# encoder_board.net
KiCad netlist of a schematic drawn in EAGLE
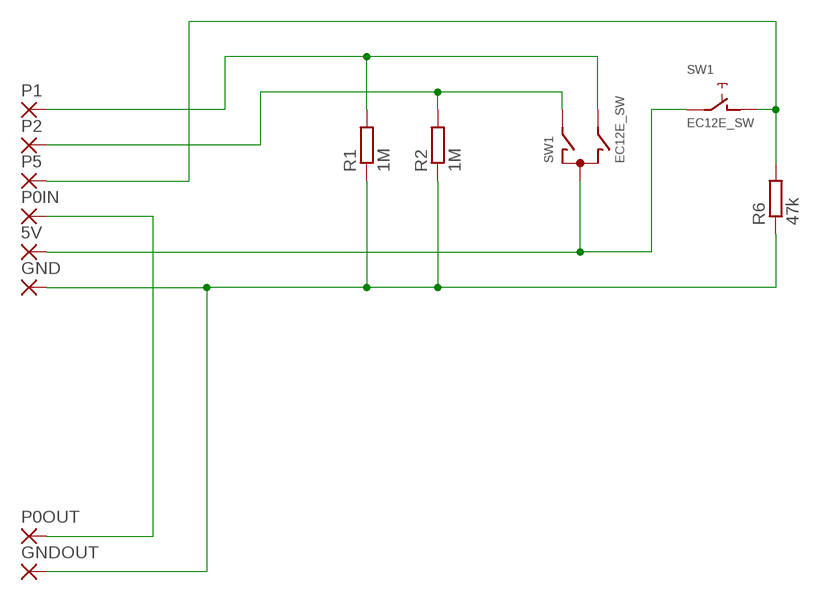
[diagram p0: schematic, sheet 1]

(export (version "E")
  (design (tool "Eeschema 10.0.6"))
  (components
    (comp (ref "5V")
      (value "2,54/0,8")
      (footprint "eagle-import:2,54_0,8")
      (libsource (lib "eagle-import") (part "2,54/0,8"))
    )
    (comp (ref "GND")
      (value "2,54/0,8")
      (footprint "eagle-import:2,54_0,8")
      (libsource (lib "eagle-import") (part "2,54/0,8"))
    )
    (comp (ref "GNDOUT")
      (value "2,54/0,8")
      (footprint "eagle-import:2,54_0,8")
      (libsource (lib "eagle-import") (part "2,54/0,8"))
    )
    (comp (ref "P0IN")
      (value "2,54/0,8")
      (footprint "eagle-import:2,54_0,8")
      (libsource (lib "eagle-import") (part "2,54/0,8"))
    )
    (comp (ref "P0OUT")
      (value "2,54/0,8")
      (footprint "eagle-import:2,54_0,8")
      (libsource (lib "eagle-import") (part "2,54/0,8"))
    )
    (comp (ref "P1")
      (value "2,54/0,8")
      (footprint "eagle-import:2,54_0,8")
      (libsource (lib "eagle-import") (part "2,54/0,8"))
    )
    (comp (ref "P2")
      (value "2,54/0,8")
      (footprint "eagle-import:2,54_0,8")
      (libsource (lib "eagle-import") (part "2,54/0,8"))
    )
    (comp (ref "P5")
      (value "2,54/0,8")
      (footprint "eagle-import:2,54_0,8")
      (libsource (lib "eagle-import") (part "2,54/0,8"))
    )
    (comp (ref "R1")
      (value "1M")
      (footprint "eagle-import:0204_7")
      (libsource (lib "eagle-import") (part "R-EU_0204/7"))
    )
    (comp (ref "R2")
      (value "1M")
      (footprint "eagle-import:0204_7")
      (libsource (lib "eagle-import") (part "R-EU_0204/7"))
    )
    (comp (ref "R6")
      (value "47k")
      (footprint "eagle-import:0204_7")
      (libsource (lib "eagle-import") (part "R-EU_0204/7"))
    )
    (comp (ref "SW1")
      (value "EC12E_SW")
      (footprint "eagle-import:ALPS_EC12E_SW")
      (fields (field (name "MPN") "EC12E2424407"))
      (libsource (lib "eagle-import") (part "EC12E_SW"))
    )
  )
  (nets
    (net (code "1") (name "Net-(5V-P)") (class "Default")
      (node (ref "5V") (pin "1") (pinfunction "P_1") (pintype "passive"))
      (node (ref "SW1") (pin "C") (pinfunction "C_C") (pintype "passive"))
      (node (ref "SW1") (pin "E") (pinfunction "2_E") (pintype "passive"))
    )
    (net (code "2") (name "Net-(GND-P)") (class "Default")
      (node (ref "GND") (pin "1") (pinfunction "P_1") (pintype "passive"))
      (node (ref "GNDOUT") (pin "1") (pinfunction "P_1") (pintype "passive"))
      (node (ref "R1") (pin "1") (pinfunction "1_1") (pintype "passive"))
      (node (ref "R2") (pin "1") (pinfunction "1_1") (pintype "passive"))
      (node (ref "R6") (pin "1") (pinfunction "1_1") (pintype "passive"))
    )
    (net (code "3") (name "Net-(P0IN-P)") (class "Default")
      (node (ref "P0IN") (pin "1") (pinfunction "P_1") (pintype "passive"))
      (node (ref "P0OUT") (pin "1") (pinfunction "P_1") (pintype "passive"))
    )
    (net (code "4") (name "Net-(P1-P)") (class "Default")
      (node (ref "P1") (pin "1") (pinfunction "P_1") (pintype "passive"))
      (node (ref "R1") (pin "2") (pinfunction "2_2") (pintype "passive"))
      (node (ref "SW1") (pin "B") (pinfunction "B_B") (pintype "passive"))
    )
    (net (code "5") (name "Net-(P2-P)") (class "Default")
      (node (ref "P2") (pin "1") (pinfunction "P_1") (pintype "passive"))
      (node (ref "R2") (pin "2") (pinfunction "2_2") (pintype "passive"))
      (node (ref "SW1") (pin "A") (pinfunction "A_A") (pintype "passive"))
    )
    (net (code "6") (name "Net-(P5-P)") (class "Default")
      (node (ref "P5") (pin "1") (pinfunction "P_1") (pintype "passive"))
      (node (ref "R6") (pin "2") (pinfunction "2_2") (pintype "passive"))
      (node (ref "SW1") (pin "D") (pinfunction "1_D") (pintype "passive"))
    )
  )
)
